# dw-probe-v1_1.net
KiCad netlist of a schematic drawn in EAGLE
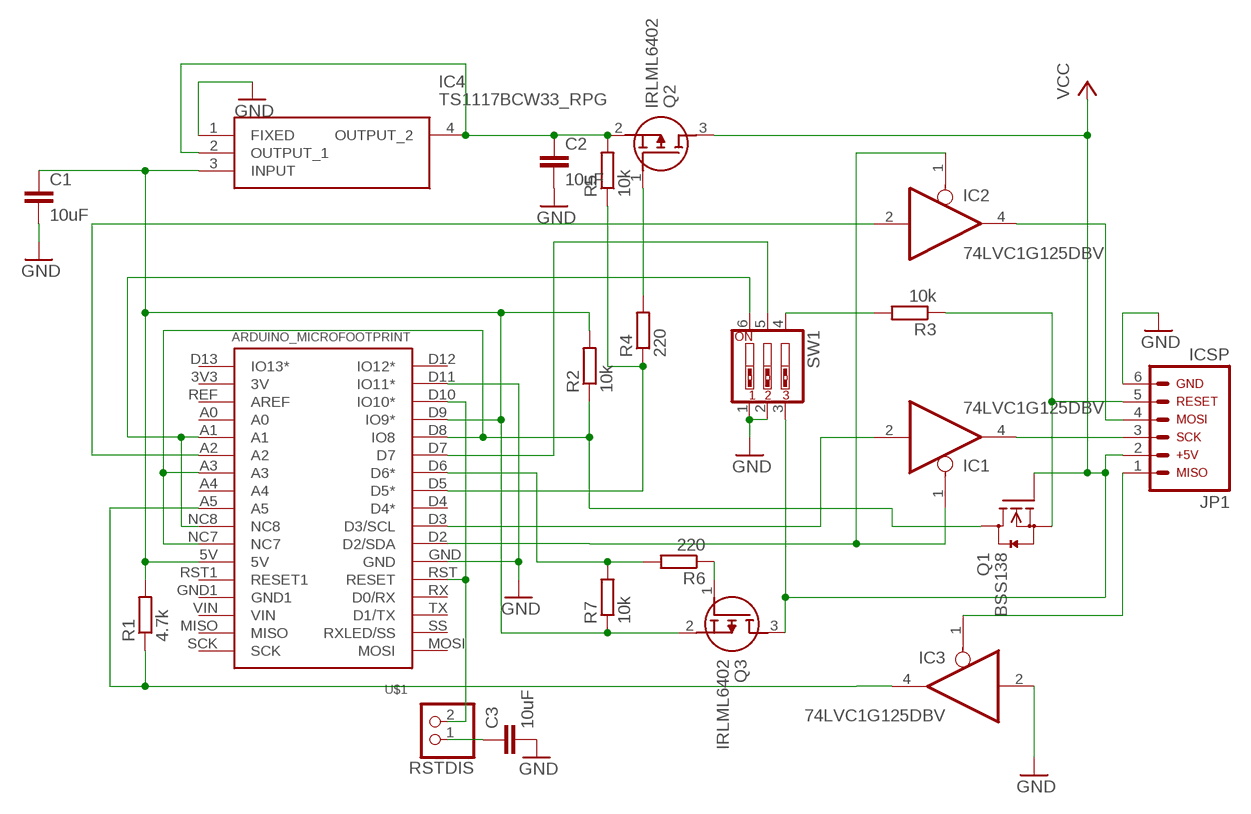
[diagram p0: schematic, sheet 1]

(export (version "E")
  (design (tool "Eeschema 10.0.6"))
  (components
    (comp (ref "C1")
      (value "10uF")
      (footprint "eagle-import:C0805")
      (libsource (lib "eagle-import") (part "C-EUC0805"))
    )
    (comp (ref "C2")
      (value "10uF")
      (footprint "eagle-import:C0805")
      (libsource (lib "eagle-import") (part "C-EUC0805"))
    )
    (comp (ref "C3")
      (value "10uF")
      (footprint "eagle-import:C0805")
      (libsource (lib "eagle-import") (part "C-EUC0805"))
    )
    (comp (ref "IC1")
      (value "74LVC1G125DBV")
      (footprint "eagle-import:SOT23-5")
      (libsource (lib "eagle-import") (part "741G125DBVLVC"))
    )
    (comp (ref "IC2")
      (value "74LVC1G125DBV")
      (footprint "eagle-import:SOT23-5")
      (libsource (lib "eagle-import") (part "741G125DBVLVC"))
    )
    (comp (ref "IC3")
      (value "74LVC1G125DBV")
      (footprint "eagle-import:SOT23-5")
      (libsource (lib "eagle-import") (part "741G125DBVLVC"))
    )
    (comp (ref "IC4")
      (value "TS1117BCW33_RPG")
      (footprint "eagle-import:SOT230P700X190-4N")
      (fields
        (field (name "ARROW_PART_NUMBER") "TS1117BCW33 RPG")
        (field (name "MOUSER_PART_NUMBER") "821-TS1117BCW33RPG")
      )
      (libsource (lib "eagle-import") (part "TS1117BCW33_RPG"))
    )
    (comp (ref "JP1")
      (value "ARDUINO_CONN-ICSP")
      (footprint "eagle-import:CONN-2X03")
      (libsource (lib "eagle-import") (part "ARDUINO_CONN-ICSP"))
    )
    (comp (ref "Q1")
      (value "BSS138")
      (footprint "eagle-import:SOT23")
      (libsource (lib "eagle-import") (part "BSS138"))
    )
    (comp (ref "Q2")
      (value "IRLML6402")
      (footprint "eagle-import:SOT95P237X112-3N")
      (libsource (lib "eagle-import") (part "IRLML6402"))
    )
    (comp (ref "Q3")
      (value "IRLML6402")
      (footprint "eagle-import:SOT95P237X112-3N")
      (libsource (lib "eagle-import") (part "IRLML6402"))
    )
    (comp (ref "R1")
      (value "4.7k")
      (footprint "eagle-import:R0805")
      (libsource (lib "eagle-import") (part "R-EU_R0805"))
    )
    (comp (ref "R2")
      (value "10k")
      (footprint "eagle-import:R0805")
      (libsource (lib "eagle-import") (part "R-EU_R0805"))
    )
    (comp (ref "R3")
      (value "10k")
      (footprint "eagle-import:R0805")
      (libsource (lib "eagle-import") (part "R-EU_R0805"))
    )
    (comp (ref "R4")
      (value "220")
      (footprint "eagle-import:R0805")
      (libsource (lib "eagle-import") (part "R-EU_R0805"))
    )
    (comp (ref "R5")
      (value "10k")
      (footprint "eagle-import:R0805")
      (libsource (lib "eagle-import") (part "R-EU_R0805"))
    )
    (comp (ref "R6")
      (value "220")
      (footprint "eagle-import:R0805")
      (libsource (lib "eagle-import") (part "R-EU_R0805"))
    )
    (comp (ref "R7")
      (value "10k")
      (footprint "eagle-import:R0805")
      (libsource (lib "eagle-import") (part "R-EU_R0805"))
    )
    (comp (ref "RSTDIS")
      (value "PINHD-1X2")
      (footprint "eagle-import:1X02")
      (libsource (lib "eagle-import") (part "PINHD-1X2"))
    )
    (comp (ref "SW1")
      (value "SW_DIP-3")
      (footprint "eagle-import:EDG-03")
      (libsource (lib "eagle-import") (part "SW_DIP-3"))
    )
    (comp (ref "U$1")
      (value "ARDUINO_MICROFOOTPRINT")
      (footprint "eagle-import:ARDUINO-MICRO")
      (libsource (lib "eagle-import") (part "ARDUINO_MICROFOOTPRINT"))
    )
  )
  (nets
    (net (code "1") (name "GND") (class "Default")
      (node (ref "C1") (pin "2") (pinfunction "2_2") (pintype "passive"))
      (node (ref "C2") (pin "2") (pinfunction "2_2") (pintype "passive"))
      (node (ref "C3") (pin "2") (pinfunction "2_2") (pintype "passive"))
      (node (ref "IC3") (pin "2") (pinfunction "I_2") (pintype "input"))
      (node (ref "IC4") (pin "1") (pinfunction "FIXED_1") (pintype "bidirectional"))
      (node (ref "JP1") (pin "6") (pinfunction "6_6") (pintype "passive"))
      (node (ref "SW1") (pin "1") (pinfunction "1_1") (pintype "passive"))
      (node (ref "SW1") (pin "2") (pinfunction "2_2") (pintype "passive"))
      (node (ref "U$1") (pin "D11") (pinfunction "IO11*_D11") (pintype "bidirectional"))
      (node (ref "U$1") (pin "GND") (pinfunction "GND_GND") (pintype "bidirectional"))
    )
    (net (code "2") (name "Net-(C3-Pad1)") (class "Default")
      (node (ref "C3") (pin "1") (pinfunction "1_1") (pintype "passive"))
      (node (ref "RSTDIS") (pin "1") (pinfunction "1_1") (pintype "passive"))
    )
    (net (code "3") (name "Net-(IC1A-I)") (class "Default")
      (node (ref "IC1") (pin "2") (pinfunction "I_2") (pintype "input"))
      (node (ref "U$1") (pin "D3") (pinfunction "D3/SCL_D3") (pintype "bidirectional"))
    )
    (net (code "4") (name "Net-(IC1A-O)") (class "Default")
      (node (ref "IC1") (pin "4") (pinfunction "O_4") (pintype "tri_state"))
      (node (ref "JP1") (pin "3") (pinfunction "3_3") (pintype "passive"))
    )
    (net (code "5") (name "Net-(IC1A-OE)") (class "Default")
      (node (ref "IC1") (pin "1") (pinfunction "OE_1") (pintype "input"))
      (node (ref "IC2") (pin "1") (pinfunction "OE_1") (pintype "input"))
      (node (ref "U$1") (pin "D2") (pinfunction "D2/SDA_D2") (pintype "bidirectional"))
    )
    (net (code "6") (name "Net-(IC2A-I)") (class "Default")
      (node (ref "IC2") (pin "2") (pinfunction "I_2") (pintype "input"))
      (node (ref "U$1") (pin "A2") (pinfunction "A2_A2") (pintype "bidirectional"))
    )
    (net (code "7") (name "Net-(IC2A-O)") (class "Default")
      (node (ref "IC2") (pin "4") (pinfunction "O_4") (pintype "tri_state"))
      (node (ref "JP1") (pin "4") (pinfunction "4_4") (pintype "passive"))
    )
    (net (code "8") (name "Net-(IC3A-O)") (class "Default")
      (node (ref "IC3") (pin "4") (pinfunction "O_4") (pintype "tri_state"))
      (node (ref "R1") (pin "1") (pinfunction "1_1") (pintype "passive"))
      (node (ref "U$1") (pin "A5") (pinfunction "A5_A5") (pintype "bidirectional"))
    )
    (net (code "9") (name "Net-(IC3A-OE)") (class "Default")
      (node (ref "IC3") (pin "1") (pinfunction "OE_1") (pintype "input"))
      (node (ref "JP1") (pin "1") (pinfunction "1_1") (pintype "passive"))
    )
    (net (code "10") (name "Net-(IC4-INPUT)") (class "Default")
      (node (ref "C1") (pin "1") (pinfunction "1_1") (pintype "passive"))
      (node (ref "IC4") (pin "3") (pinfunction "INPUT_3") (pintype "bidirectional"))
      (node (ref "Q3") (pin "2") (pinfunction "S_2") (pintype "bidirectional"))
      (node (ref "R1") (pin "2") (pinfunction "2_2") (pintype "passive"))
      (node (ref "R2") (pin "2") (pinfunction "2_2") (pintype "passive"))
      (node (ref "R7") (pin "1") (pinfunction "1_1") (pintype "passive"))
      (node (ref "U$1") (pin "5V") (pinfunction "5V_5V") (pintype "bidirectional"))
      (node (ref "U$1") (pin "D9") (pinfunction "IO9*_D9") (pintype "bidirectional"))
    )
    (net (code "11") (name "Net-(IC4-OUTPUT_1)") (class "Default")
      (node (ref "C2") (pin "1") (pinfunction "1_1") (pintype "passive"))
      (node (ref "IC4") (pin "2") (pinfunction "OUTPUT_1_2") (pintype "bidirectional"))
      (node (ref "IC4") (pin "4") (pinfunction "OUTPUT_2_4") (pintype "bidirectional"))
      (node (ref "Q2") (pin "2") (pinfunction "S_2") (pintype "bidirectional"))
      (node (ref "R5") (pin "2") (pinfunction "2_2") (pintype "passive"))
    )
    (net (code "12") (name "Net-(Q1-D)") (class "Default")
      (node (ref "Q1") (pin "3") (pinfunction "D_3") (pintype "passive"))
      (node (ref "R2") (pin "1") (pinfunction "1_1") (pintype "passive"))
      (node (ref "U$1") (pin "A3") (pinfunction "A3_A3") (pintype "bidirectional"))
      (node (ref "U$1") (pin "D8") (pinfunction "IO8_D8") (pintype "bidirectional"))
      (node (ref "U$1") (pin "NC7") (pinfunction "NC7_NC7") (pintype "bidirectional"))
    )
    (net (code "13") (name "Net-(Q1-S)") (class "Default")
      (node (ref "JP1") (pin "5") (pinfunction "5_5") (pintype "passive"))
      (node (ref "Q1") (pin "2") (pinfunction "S_2") (pintype "passive"))
      (node (ref "R3") (pin "1") (pinfunction "1_1") (pintype "passive"))
    )
    (net (code "14") (name "Net-(Q2-G)") (class "Default")
      (node (ref "Q2") (pin "1") (pinfunction "G_1") (pintype "bidirectional"))
      (node (ref "R4") (pin "2") (pinfunction "2_2") (pintype "passive"))
    )
    (net (code "15") (name "Net-(Q3-G)") (class "Default")
      (node (ref "Q3") (pin "1") (pinfunction "G_1") (pintype "bidirectional"))
      (node (ref "R6") (pin "1") (pinfunction "1_1") (pintype "passive"))
    )
    (net (code "16") (name "Net-(R3-Pad2)") (class "Default")
      (node (ref "R3") (pin "2") (pinfunction "2_2") (pintype "passive"))
      (node (ref "SW1") (pin "4") (pinfunction "4_4") (pintype "passive"))
    )
    (net (code "17") (name "Net-(SW1-Pad5)") (class "Default")
      (node (ref "SW1") (pin "5") (pinfunction "5_5") (pintype "passive"))
      (node (ref "U$1") (pin "D7") (pinfunction "D7_D7") (pintype "bidirectional"))
    )
    (net (code "18") (name "Net-(SW1-Pad6)") (class "Default")
      (node (ref "SW1") (pin "6") (pinfunction "6_6") (pintype "passive"))
      (node (ref "U$1") (pin "A1") (pinfunction "A1_A1") (pintype "bidirectional"))
      (node (ref "U$1") (pin "NC8") (pinfunction "NC8_NC8") (pintype "bidirectional"))
    )
    (net (code "19") (name "Net-(U$1-D5*)") (class "Default")
      (node (ref "R4") (pin "1") (pinfunction "1_1") (pintype "passive"))
      (node (ref "R5") (pin "1") (pinfunction "1_1") (pintype "passive"))
      (node (ref "U$1") (pin "D5") (pinfunction "D5*_D5") (pintype "bidirectional"))
    )
    (net (code "20") (name "Net-(U$1-D6*)") (class "Default")
      (node (ref "R6") (pin "2") (pinfunction "2_2") (pintype "passive"))
      (node (ref "R7") (pin "2") (pinfunction "2_2") (pintype "passive"))
      (node (ref "U$1") (pin "D6") (pinfunction "D6*_D6") (pintype "bidirectional"))
    )
    (net (code "21") (name "Net-(U$1-IO10*)") (class "Default")
      (node (ref "RSTDIS") (pin "2") (pinfunction "2_2") (pintype "passive"))
      (node (ref "U$1") (pin "D10") (pinfunction "IO10*_D10") (pintype "bidirectional"))
      (node (ref "U$1") (pin "RST") (pinfunction "RESET_RST") (pintype "bidirectional"))
    )
    (net (code "22") (name "VCC") (class "Default")
      (node (ref "JP1") (pin "2") (pinfunction "2_2") (pintype "passive"))
      (node (ref "Q1") (pin "1") (pinfunction "G_1") (pintype "passive"))
      (node (ref "Q2") (pin "3") (pinfunction "D_3") (pintype "bidirectional"))
      (node (ref "Q3") (pin "3") (pinfunction "D_3") (pintype "bidirectional"))
      (node (ref "SW1") (pin "3") (pinfunction "3_3") (pintype "passive"))
    )
    (net (code "23") (name "unconnected-(U$1-3V-Pad3V3)") (class "Default")
      (node (ref "U$1") (pin "3V3") (pinfunction "3V_3V3") (pintype "bidirectional"))
    )
    (net (code "24") (name "unconnected-(U$1-AREF-PadREF)") (class "Default")
      (node (ref "U$1") (pin "REF") (pinfunction "AREF_REF") (pintype "bidirectional"))
    )
    (net (code "25") (name "unconnected-(U$1-D0{slash}RX-PadRX)") (class "Default")
      (node (ref "U$1") (pin "RX") (pinfunction "D0/RX_RX") (pintype "bidirectional"))
    )
    (net (code "26") (name "unconnected-(U$1-D1{slash}TX-PadTX)") (class "Default")
      (node (ref "U$1") (pin "TX") (pinfunction "D1/TX_TX") (pintype "bidirectional"))
    )
    (net (code "27") (name "unconnected-(U$1-D4*-PadD4)") (class "Default")
      (node (ref "U$1") (pin "D4") (pinfunction "D4*_D4") (pintype "bidirectional"))
    )
    (net (code "28") (name "unconnected-(U$1-IO12*-PadD12)") (class "Default")
      (node (ref "U$1") (pin "D12") (pinfunction "IO12*_D12") (pintype "bidirectional"))
    )
    (net (code "29") (name "unconnected-(U$1-IO13*-PadD13)") (class "Default")
      (node (ref "U$1") (pin "D13") (pinfunction "IO13*_D13") (pintype "bidirectional"))
    )
    (net (code "30") (name "unconnected-(U$1-PadA0)") (class "Default")
      (node (ref "U$1") (pin "A0") (pinfunction "A0_A0") (pintype "bidirectional"))
    )
    (net (code "31") (name "unconnected-(U$1-PadA4)") (class "Default")
      (node (ref "U$1") (pin "A4") (pinfunction "A4_A4") (pintype "bidirectional"))
    )
    (net (code "32") (name "unconnected-(U$1-PadGND1)") (class "Default")
      (node (ref "U$1") (pin "GND1") (pinfunction "GND1_GND1") (pintype "bidirectional"))
    )
    (net (code "33") (name "unconnected-(U$1-PadMISO)") (class "Default")
      (node (ref "U$1") (pin "MISO") (pinfunction "MISO_MISO") (pintype "bidirectional"))
    )
    (net (code "34") (name "unconnected-(U$1-PadMOSI)") (class "Default")
      (node (ref "U$1") (pin "MOSI") (pinfunction "MOSI_MOSI") (pintype "bidirectional"))
    )
    (net (code "35") (name "unconnected-(U$1-PadSCK)") (class "Default")
      (node (ref "U$1") (pin "SCK") (pinfunction "SCK_SCK") (pintype "bidirectional"))
    )
    (net (code "36") (name "unconnected-(U$1-PadVIN)") (class "Default")
      (node (ref "U$1") (pin "VIN") (pinfunction "VIN_VIN") (pintype "bidirectional"))
    )
    (net (code "37") (name "unconnected-(U$1-RESET1-PadRST1)") (class "Default")
      (node (ref "U$1") (pin "RST1") (pinfunction "RESET1_RST1") (pintype "bidirectional"))
    )
    (net (code "38") (name "unconnected-(U$1-RXLED{slash}SS-PadSS)") (class "Default")
      (node (ref "U$1") (pin "SS") (pinfunction "RXLED/SS_SS") (pintype "bidirectional"))
    )
  )
)
